# DriverOK-DemuxOK-VIA71.net
KiCad netlist of a schematic drawn in EAGLE
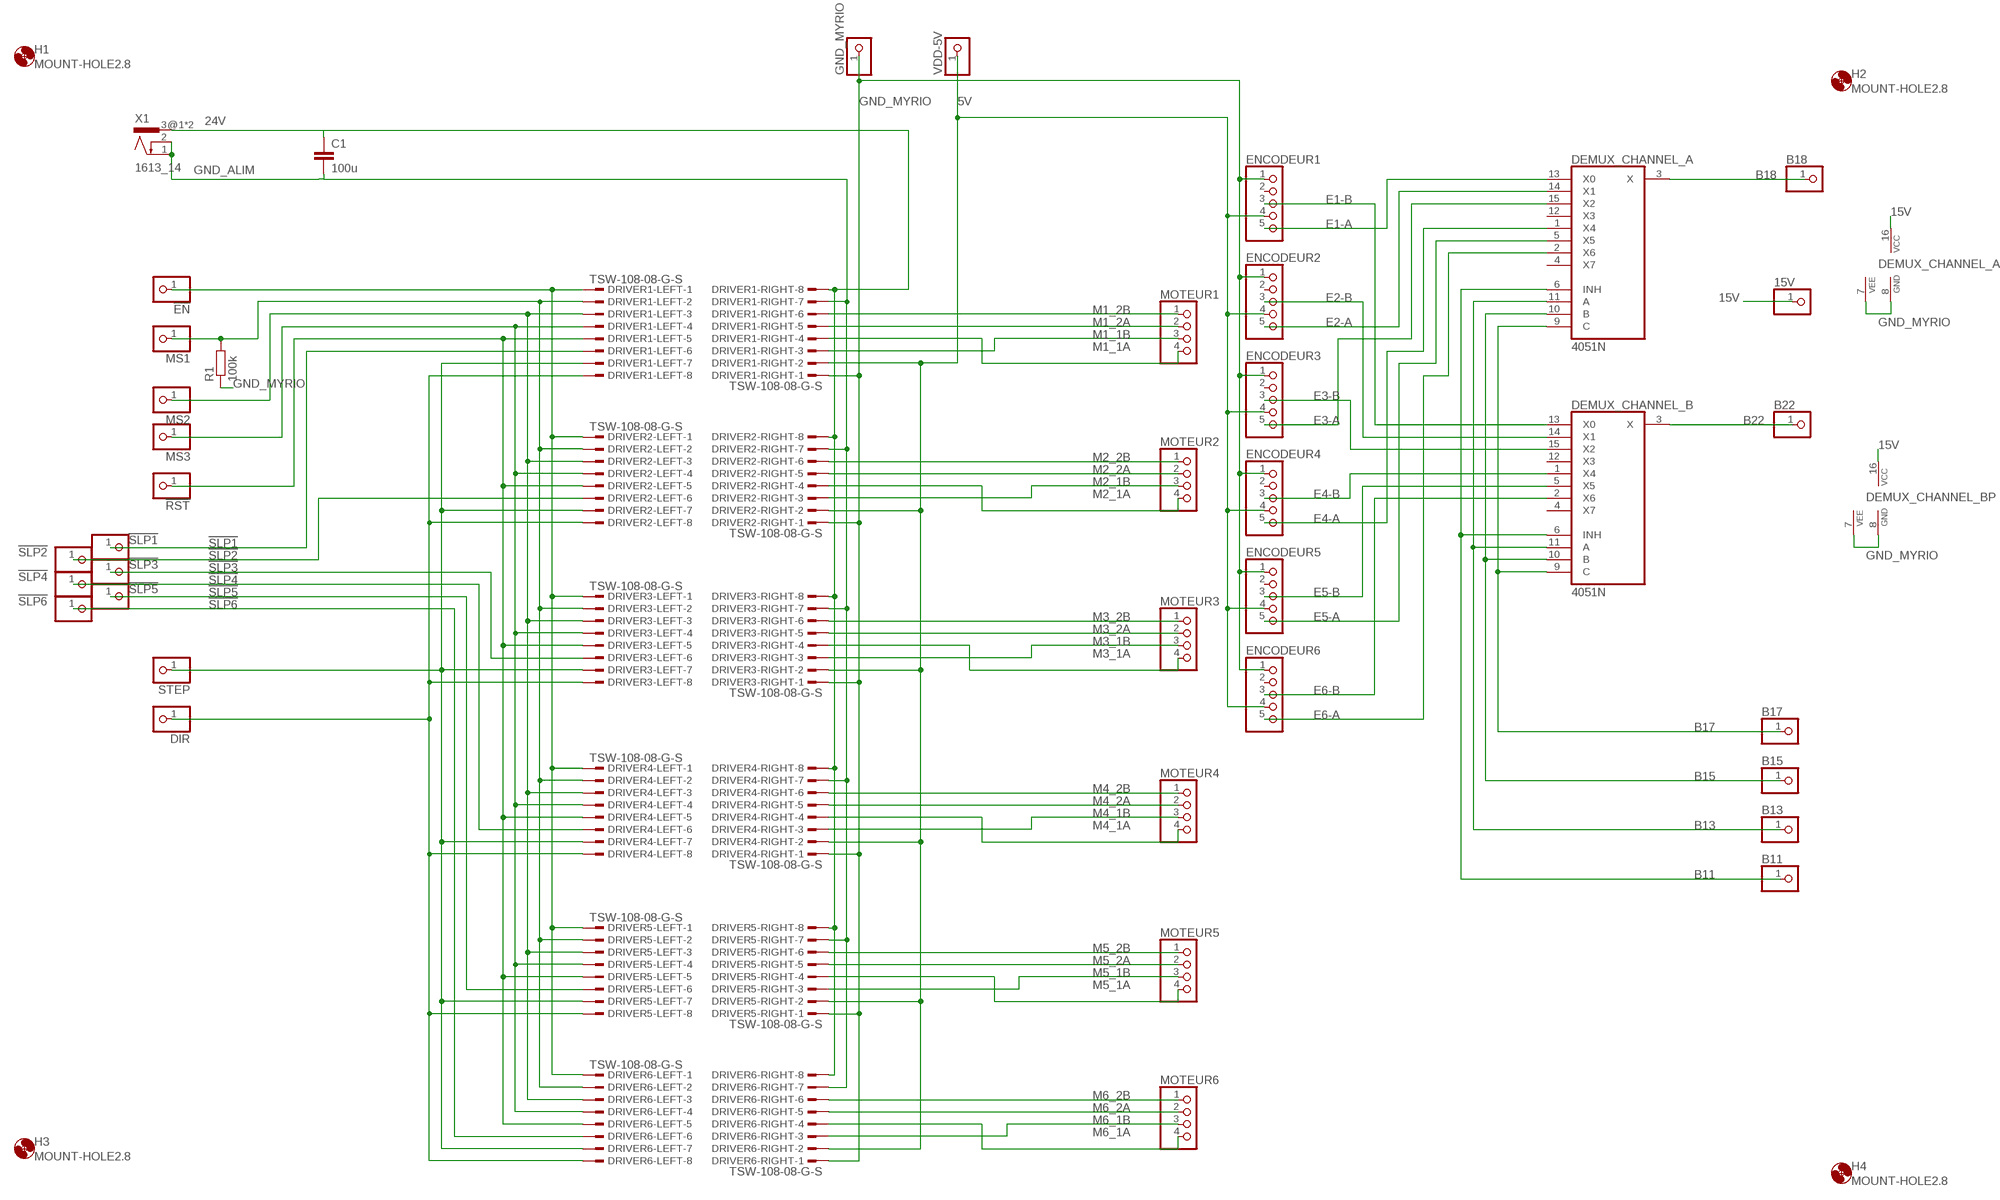
[diagram p0: schematic, sheet 1]

(export (version "E")
  (design (tool "Eeschema 10.0.6"))
  (components
    (comp (ref "!EN")
      (value "PINHD-1X1")
      (footprint "eagle-import:1X01")
      (libsource (lib "eagle-import") (part "PINHD-1X1"))
    )
    (comp (ref "!RST")
      (value "PINHD-1X1")
      (footprint "eagle-import:1X01")
      (libsource (lib "eagle-import") (part "PINHD-1X1"))
    )
    (comp (ref "!SLP1")
      (value "PINHD-1X1")
      (footprint "eagle-import:1X01")
      (libsource (lib "eagle-import") (part "PINHD-1X1"))
    )
    (comp (ref "!SLP2")
      (value "PINHD-1X1")
      (footprint "eagle-import:1X01")
      (libsource (lib "eagle-import") (part "PINHD-1X1"))
    )
    (comp (ref "!SLP3")
      (value "PINHD-1X1")
      (footprint "eagle-import:1X01")
      (libsource (lib "eagle-import") (part "PINHD-1X1"))
    )
    (comp (ref "!SLP4")
      (value "PINHD-1X1")
      (footprint "eagle-import:1X01")
      (libsource (lib "eagle-import") (part "PINHD-1X1"))
    )
    (comp (ref "!SLP5")
      (value "PINHD-1X1")
      (footprint "eagle-import:1X01")
      (libsource (lib "eagle-import") (part "PINHD-1X1"))
    )
    (comp (ref "!SLP6")
      (value "PINHD-1X1")
      (footprint "eagle-import:1X01")
      (libsource (lib "eagle-import") (part "PINHD-1X1"))
    )
    (comp (ref "15V")
      (value "PINHD-1X1")
      (footprint "eagle-import:1X01")
      (libsource (lib "eagle-import") (part "PINHD-1X1"))
    )
    (comp (ref "B11")
      (value "PINHD-1X1")
      (footprint "eagle-import:1X01")
      (libsource (lib "eagle-import") (part "PINHD-1X1"))
    )
    (comp (ref "B13")
      (value "PINHD-1X1")
      (footprint "eagle-import:1X01")
      (libsource (lib "eagle-import") (part "PINHD-1X1"))
    )
    (comp (ref "B15")
      (value "PINHD-1X1")
      (footprint "eagle-import:1X01")
      (libsource (lib "eagle-import") (part "PINHD-1X1"))
    )
    (comp (ref "B17")
      (value "PINHD-1X1")
      (footprint "eagle-import:1X01")
      (libsource (lib "eagle-import") (part "PINHD-1X1"))
    )
    (comp (ref "B18")
      (value "PINHD-1X1")
      (footprint "eagle-import:1X01")
      (libsource (lib "eagle-import") (part "PINHD-1X1"))
    )
    (comp (ref "B22")
      (value "PINHD-1X1")
      (footprint "eagle-import:1X01")
      (libsource (lib "eagle-import") (part "PINHD-1X1"))
    )
    (comp (ref "C1")
      (value "100u")
      (footprint "eagle-import:C025-025X050")
      (libsource (lib "eagle-import") (part "C-EU025-025X050"))
    )
    (comp (ref "DEMUX_CHANNEL_A")
      (value "4051N")
      (footprint "eagle-import:DIL16")
      (libsource (lib "eagle-import") (part "4051N"))
    )
    (comp (ref "DEMUX_CHANNEL_B")
      (value "4051N")
      (footprint "eagle-import:DIL16")
      (libsource (lib "eagle-import") (part "4051N"))
    )
    (comp (ref "DIR")
      (value "PINHD-1X1")
      (footprint "eagle-import:1X01")
      (libsource (lib "eagle-import") (part "PINHD-1X1"))
    )
    (comp (ref "DRIVER1-LEFT")
      (value "TSW-108-08-G-S")
      (footprint "eagle-import:TSW-108-XX-G-S")
      (fields (field (name "MF") "Samtec Inc.") (field (name "MPN") "TSW-108-07-G-S"))
      (libsource (lib "eagle-import") (part "TSW-108--G-S08"))
    )
    (comp (ref "DRIVER1-RIGHT")
      (value "TSW-108-08-G-S")
      (footprint "eagle-import:TSW-108-XX-G-S")
      (fields (field (name "MF") "Samtec Inc.") (field (name "MPN") "TSW-108-07-G-S"))
      (libsource (lib "eagle-import") (part "TSW-108--G-S08"))
    )
    (comp (ref "DRIVER2-LEFT")
      (value "TSW-108-08-G-S")
      (footprint "eagle-import:TSW-108-XX-G-S")
      (fields (field (name "MF") "Samtec Inc.") (field (name "MPN") "TSW-108-07-G-S"))
      (libsource (lib "eagle-import") (part "TSW-108--G-S08"))
    )
    (comp (ref "DRIVER2-RIGHT")
      (value "TSW-108-08-G-S")
      (footprint "eagle-import:TSW-108-XX-G-S")
      (fields (field (name "MF") "Samtec Inc.") (field (name "MPN") "TSW-108-07-G-S"))
      (libsource (lib "eagle-import") (part "TSW-108--G-S08"))
    )
    (comp (ref "DRIVER3-LEFT")
      (value "TSW-108-08-G-S")
      (footprint "eagle-import:TSW-108-XX-G-S")
      (fields (field (name "MF") "Samtec Inc.") (field (name "MPN") "TSW-108-07-G-S"))
      (libsource (lib "eagle-import") (part "TSW-108--G-S08"))
    )
    (comp (ref "DRIVER3-RIGHT")
      (value "TSW-108-08-G-S")
      (footprint "eagle-import:TSW-108-XX-G-S")
      (fields (field (name "MF") "Samtec Inc.") (field (name "MPN") "TSW-108-07-G-S"))
      (libsource (lib "eagle-import") (part "TSW-108--G-S08"))
    )
    (comp (ref "DRIVER4-LEFT")
      (value "TSW-108-08-G-S")
      (footprint "eagle-import:TSW-108-XX-G-S")
      (fields (field (name "MF") "Samtec Inc.") (field (name "MPN") "TSW-108-07-G-S"))
      (libsource (lib "eagle-import") (part "TSW-108--G-S08"))
    )
    (comp (ref "DRIVER4-RIGHT")
      (value "TSW-108-08-G-S")
      (footprint "eagle-import:TSW-108-XX-G-S")
      (fields (field (name "MF") "Samtec Inc.") (field (name "MPN") "TSW-108-07-G-S"))
      (libsource (lib "eagle-import") (part "TSW-108--G-S08"))
    )
    (comp (ref "DRIVER5-LEFT")
      (value "TSW-108-08-G-S")
      (footprint "eagle-import:TSW-108-XX-G-S")
      (fields (field (name "MF") "Samtec Inc.") (field (name "MPN") "TSW-108-07-G-S"))
      (libsource (lib "eagle-import") (part "TSW-108--G-S08"))
    )
    (comp (ref "DRIVER5-RIGHT")
      (value "TSW-108-08-G-S")
      (footprint "eagle-import:TSW-108-XX-G-S")
      (fields (field (name "MF") "Samtec Inc.") (field (name "MPN") "TSW-108-07-G-S"))
      (libsource (lib "eagle-import") (part "TSW-108--G-S08"))
    )
    (comp (ref "DRIVER6-LEFT")
      (value "TSW-108-08-G-S")
      (footprint "eagle-import:TSW-108-XX-G-S")
      (fields (field (name "MF") "Samtec Inc.") (field (name "MPN") "TSW-108-07-G-S"))
      (libsource (lib "eagle-import") (part "TSW-108--G-S08"))
    )
    (comp (ref "DRIVER6-RIGHT")
      (value "TSW-108-08-G-S")
      (footprint "eagle-import:TSW-108-XX-G-S")
      (fields (field (name "MF") "Samtec Inc.") (field (name "MPN") "TSW-108-07-G-S"))
      (libsource (lib "eagle-import") (part "TSW-108--G-S08"))
    )
    (comp (ref "ENCODEUR1")
      (value "PINHD-1X5")
      (footprint "eagle-import:1X05")
      (libsource (lib "eagle-import") (part "PINHD-1X5"))
    )
    (comp (ref "ENCODEUR2")
      (value "PINHD-1X5")
      (footprint "eagle-import:1X05")
      (libsource (lib "eagle-import") (part "PINHD-1X5"))
    )
    (comp (ref "ENCODEUR3")
      (value "PINHD-1X5")
      (footprint "eagle-import:1X05")
      (libsource (lib "eagle-import") (part "PINHD-1X5"))
    )
    (comp (ref "ENCODEUR4")
      (value "PINHD-1X5")
      (footprint "eagle-import:1X05")
      (libsource (lib "eagle-import") (part "PINHD-1X5"))
    )
    (comp (ref "ENCODEUR5")
      (value "PINHD-1X5")
      (footprint "eagle-import:1X05")
      (libsource (lib "eagle-import") (part "PINHD-1X5"))
    )
    (comp (ref "ENCODEUR6")
      (value "PINHD-1X5")
      (footprint "eagle-import:1X05")
      (libsource (lib "eagle-import") (part "PINHD-1X5"))
    )
    (comp (ref "GND_MYRIO")
      (value "PINHD-1X1")
      (footprint "eagle-import:1X01")
      (libsource (lib "eagle-import") (part "PINHD-1X1"))
    )
    (comp (ref "H1")
      (value "MOUNT-HOLE2.8")
      (footprint "eagle-import:2,8")
      (libsource (lib "eagle-import") (part "MOUNT-HOLE2.8"))
    )
    (comp (ref "H2")
      (value "MOUNT-HOLE2.8")
      (footprint "eagle-import:2,8")
      (libsource (lib "eagle-import") (part "MOUNT-HOLE2.8"))
    )
    (comp (ref "H3")
      (value "MOUNT-HOLE2.8")
      (footprint "eagle-import:2,8")
      (libsource (lib "eagle-import") (part "MOUNT-HOLE2.8"))
    )
    (comp (ref "H4")
      (value "MOUNT-HOLE2.8")
      (footprint "eagle-import:2,8")
      (libsource (lib "eagle-import") (part "MOUNT-HOLE2.8"))
    )
    (comp (ref "MOTEUR1")
      (value "PINHD-1X4")
      (footprint "eagle-import:1X04")
      (libsource (lib "eagle-import") (part "PINHD-1X4"))
    )
    (comp (ref "MOTEUR2")
      (value "PINHD-1X4")
      (footprint "eagle-import:1X04")
      (libsource (lib "eagle-import") (part "PINHD-1X4"))
    )
    (comp (ref "MOTEUR3")
      (value "PINHD-1X4")
      (footprint "eagle-import:1X04")
      (libsource (lib "eagle-import") (part "PINHD-1X4"))
    )
    (comp (ref "MOTEUR4")
      (value "PINHD-1X4")
      (footprint "eagle-import:1X04")
      (libsource (lib "eagle-import") (part "PINHD-1X4"))
    )
    (comp (ref "MOTEUR5")
      (value "PINHD-1X4")
      (footprint "eagle-import:1X04")
      (libsource (lib "eagle-import") (part "PINHD-1X4"))
    )
    (comp (ref "MOTEUR6")
      (value "PINHD-1X4")
      (footprint "eagle-import:1X04")
      (libsource (lib "eagle-import") (part "PINHD-1X4"))
    )
    (comp (ref "MS1")
      (value "PINHD-1X1")
      (footprint "eagle-import:1X01")
      (libsource (lib "eagle-import") (part "PINHD-1X1"))
    )
    (comp (ref "MS2")
      (value "PINHD-1X1")
      (footprint "eagle-import:1X01")
      (libsource (lib "eagle-import") (part "PINHD-1X1"))
    )
    (comp (ref "MS3")
      (value "PINHD-1X1")
      (footprint "eagle-import:1X01")
      (libsource (lib "eagle-import") (part "PINHD-1X1"))
    )
    (comp (ref "R1")
      (value "100k")
      (footprint "eagle-import:0207_10")
      (libsource (lib "eagle-import") (part "R-EU_0207/10"))
    )
    (comp (ref "STEP")
      (value "PINHD-1X1")
      (footprint "eagle-import:1X01")
      (libsource (lib "eagle-import") (part "PINHD-1X1"))
    )
    (comp (ref "VDD-5V")
      (value "PINHD-1X1")
      (footprint "eagle-import:1X01")
      (libsource (lib "eagle-import") (part "PINHD-1X1"))
    )
    (comp (ref "X1")
      (value "1613_14")
      (footprint "eagle-import:1613_14")
      (fields (field (name "MF") "LUMBERG") (field (name "MPN") "1613 14"))
      (libsource (lib "eagle-import") (part "1613_14"))
    )
  )
  (nets
    (net (code "1") (name "/5V") (class "Default")
      (node (ref "DRIVER1-RIGHT") (pin "2") (pinfunction "1_2") (pintype "passive"))
      (node (ref "DRIVER2-RIGHT") (pin "2") (pinfunction "1_2") (pintype "passive"))
      (node (ref "DRIVER3-RIGHT") (pin "2") (pinfunction "1_2") (pintype "passive"))
      (node (ref "DRIVER4-RIGHT") (pin "2") (pinfunction "1_2") (pintype "passive"))
      (node (ref "DRIVER5-RIGHT") (pin "2") (pinfunction "1_2") (pintype "passive"))
      (node (ref "DRIVER6-RIGHT") (pin "2") (pinfunction "1_2") (pintype "passive"))
      (node (ref "ENCODEUR1") (pin "4") (pinfunction "4_4") (pintype "passive"))
      (node (ref "ENCODEUR2") (pin "4") (pinfunction "4_4") (pintype "passive"))
      (node (ref "ENCODEUR3") (pin "4") (pinfunction "4_4") (pintype "passive"))
      (node (ref "ENCODEUR4") (pin "4") (pinfunction "4_4") (pintype "passive"))
      (node (ref "ENCODEUR5") (pin "4") (pinfunction "4_4") (pintype "passive"))
      (node (ref "ENCODEUR6") (pin "4") (pinfunction "4_4") (pintype "passive"))
      (node (ref "VDD-5V") (pin "1") (pinfunction "1_1") (pintype "passive"))
    )
    (net (code "2") (name "/15V") (class "Default")
      (node (ref "15V") (pin "1") (pinfunction "1_1") (pintype "passive"))
      (node (ref "DEMUX_CHANNEL_A") (pin "16") (pinfunction "VCC_16") (pintype "power_in"))
      (node (ref "DEMUX_CHANNEL_B") (pin "16") (pinfunction "VCC_16") (pintype "power_in"))
    )
    (net (code "3") (name "/24V") (class "Default")
      (node (ref "C1") (pin "1") (pinfunction "1_1") (pintype "passive"))
      (node (ref "DRIVER1-RIGHT") (pin "8") (pinfunction "1_8") (pintype "passive"))
      (node (ref "DRIVER2-RIGHT") (pin "8") (pinfunction "1_8") (pintype "passive"))
      (node (ref "DRIVER3-RIGHT") (pin "8") (pinfunction "1_8") (pintype "passive"))
      (node (ref "DRIVER4-RIGHT") (pin "8") (pinfunction "1_8") (pintype "passive"))
      (node (ref "DRIVER5-RIGHT") (pin "8") (pinfunction "1_8") (pintype "passive"))
      (node (ref "DRIVER6-RIGHT") (pin "8") (pinfunction "1_8") (pintype "passive"))
      (node (ref "X1") (pin "3@1") (pinfunction "3_3@1") (pintype "passive"))
      (node (ref "X1") (pin "3@2") (pinfunction "3_3@2") (pintype "passive"))
    )
    (net (code "4") (name "/B11") (class "Default")
      (node (ref "B11") (pin "1") (pinfunction "1_1") (pintype "passive"))
      (node (ref "DEMUX_CHANNEL_A") (pin "6") (pinfunction "INH_6") (pintype "input"))
      (node (ref "DEMUX_CHANNEL_B") (pin "6") (pinfunction "INH_6") (pintype "input"))
    )
    (net (code "5") (name "/B13") (class "Default")
      (node (ref "B13") (pin "1") (pinfunction "1_1") (pintype "passive"))
      (node (ref "DEMUX_CHANNEL_A") (pin "11") (pinfunction "A_11") (pintype "input"))
      (node (ref "DEMUX_CHANNEL_B") (pin "11") (pinfunction "A_11") (pintype "input"))
    )
    (net (code "6") (name "/B15") (class "Default")
      (node (ref "B15") (pin "1") (pinfunction "1_1") (pintype "passive"))
      (node (ref "DEMUX_CHANNEL_A") (pin "10") (pinfunction "B_10") (pintype "input"))
      (node (ref "DEMUX_CHANNEL_B") (pin "10") (pinfunction "B_10") (pintype "input"))
    )
    (net (code "7") (name "/B17") (class "Default")
      (node (ref "B17") (pin "1") (pinfunction "1_1") (pintype "passive"))
      (node (ref "DEMUX_CHANNEL_A") (pin "9") (pinfunction "C_9") (pintype "input"))
      (node (ref "DEMUX_CHANNEL_B") (pin "9") (pinfunction "C_9") (pintype "input"))
    )
    (net (code "8") (name "/B18") (class "Default")
      (node (ref "B18") (pin "1") (pinfunction "1_1") (pintype "passive"))
      (node (ref "DEMUX_CHANNEL_A") (pin "3") (pinfunction "X_3") (pintype "bidirectional"))
    )
    (net (code "9") (name "/B22") (class "Default")
      (node (ref "B22") (pin "1") (pinfunction "1_1") (pintype "passive"))
      (node (ref "DEMUX_CHANNEL_B") (pin "3") (pinfunction "X_3") (pintype "bidirectional"))
    )
    (net (code "10") (name "/E1-A") (class "Default")
      (node (ref "DEMUX_CHANNEL_A") (pin "13") (pinfunction "X0_13") (pintype "bidirectional"))
      (node (ref "ENCODEUR1") (pin "5") (pinfunction "5_5") (pintype "passive"))
    )
    (net (code "11") (name "/E1-B") (class "Default")
      (node (ref "DEMUX_CHANNEL_B") (pin "13") (pinfunction "X0_13") (pintype "bidirectional"))
      (node (ref "ENCODEUR1") (pin "3") (pinfunction "3_3") (pintype "passive"))
    )
    (net (code "12") (name "/E2-A") (class "Default")
      (node (ref "DEMUX_CHANNEL_A") (pin "14") (pinfunction "X1_14") (pintype "bidirectional"))
      (node (ref "ENCODEUR2") (pin "5") (pinfunction "5_5") (pintype "passive"))
    )
    (net (code "13") (name "/E2-B") (class "Default")
      (node (ref "DEMUX_CHANNEL_B") (pin "14") (pinfunction "X1_14") (pintype "bidirectional"))
      (node (ref "ENCODEUR2") (pin "3") (pinfunction "3_3") (pintype "passive"))
    )
    (net (code "14") (name "/E3-A") (class "Default")
      (node (ref "DEMUX_CHANNEL_A") (pin "15") (pinfunction "X2_15") (pintype "bidirectional"))
      (node (ref "ENCODEUR3") (pin "5") (pinfunction "5_5") (pintype "passive"))
    )
    (net (code "15") (name "/E3-B") (class "Default")
      (node (ref "DEMUX_CHANNEL_B") (pin "15") (pinfunction "X2_15") (pintype "bidirectional"))
      (node (ref "ENCODEUR3") (pin "3") (pinfunction "3_3") (pintype "passive"))
    )
    (net (code "16") (name "/E4-A") (class "Default")
      (node (ref "DEMUX_CHANNEL_A") (pin "1") (pinfunction "X4_1") (pintype "bidirectional"))
      (node (ref "ENCODEUR4") (pin "5") (pinfunction "5_5") (pintype "passive"))
    )
    (net (code "17") (name "/E4-B") (class "Default")
      (node (ref "DEMUX_CHANNEL_B") (pin "1") (pinfunction "X4_1") (pintype "bidirectional"))
      (node (ref "ENCODEUR4") (pin "3") (pinfunction "3_3") (pintype "passive"))
    )
    (net (code "18") (name "/E5-A") (class "Default")
      (node (ref "DEMUX_CHANNEL_A") (pin "5") (pinfunction "X5_5") (pintype "bidirectional"))
      (node (ref "ENCODEUR5") (pin "5") (pinfunction "5_5") (pintype "passive"))
    )
    (net (code "19") (name "/E5-B") (class "Default")
      (node (ref "DEMUX_CHANNEL_B") (pin "5") (pinfunction "X5_5") (pintype "bidirectional"))
      (node (ref "ENCODEUR5") (pin "3") (pinfunction "3_3") (pintype "passive"))
    )
    (net (code "20") (name "/E6-A") (class "Default")
      (node (ref "DEMUX_CHANNEL_A") (pin "2") (pinfunction "X6_2") (pintype "bidirectional"))
      (node (ref "ENCODEUR6") (pin "5") (pinfunction "5_5") (pintype "passive"))
    )
    (net (code "21") (name "/E6-B") (class "Default")
      (node (ref "DEMUX_CHANNEL_B") (pin "2") (pinfunction "X6_2") (pintype "bidirectional"))
      (node (ref "ENCODEUR6") (pin "3") (pinfunction "3_3") (pintype "passive"))
    )
    (net (code "22") (name "/GND_ALIM") (class "Default")
      (node (ref "C1") (pin "2") (pinfunction "2_2") (pintype "passive"))
      (node (ref "DRIVER1-RIGHT") (pin "7") (pinfunction "1_7") (pintype "passive"))
      (node (ref "DRIVER2-RIGHT") (pin "7") (pinfunction "1_7") (pintype "passive"))
      (node (ref "DRIVER3-RIGHT") (pin "7") (pinfunction "1_7") (pintype "passive"))
      (node (ref "DRIVER4-RIGHT") (pin "7") (pinfunction "1_7") (pintype "passive"))
      (node (ref "DRIVER5-RIGHT") (pin "7") (pinfunction "1_7") (pintype "passive"))
      (node (ref "DRIVER6-RIGHT") (pin "7") (pinfunction "1_7") (pintype "passive"))
      (node (ref "X1") (pin "1") (pinfunction "1_1") (pintype "passive"))
      (node (ref "X1") (pin "2") (pinfunction "2_2") (pintype "passive"))
    )
    (net (code "23") (name "/GND_MYRIO") (class "Default")
      (node (ref "DEMUX_CHANNEL_A") (pin "7") (pinfunction "VEE_7") (pintype "power_in"))
      (node (ref "DEMUX_CHANNEL_A") (pin "8") (pinfunction "GND_8") (pintype "power_in"))
      (node (ref "DEMUX_CHANNEL_B") (pin "7") (pinfunction "VEE_7") (pintype "power_in"))
      (node (ref "DEMUX_CHANNEL_B") (pin "8") (pinfunction "GND_8") (pintype "power_in"))
      (node (ref "DRIVER1-RIGHT") (pin "1") (pinfunction "1_1") (pintype "passive"))
      (node (ref "DRIVER2-RIGHT") (pin "1") (pinfunction "1_1") (pintype "passive"))
      (node (ref "DRIVER3-RIGHT") (pin "1") (pinfunction "1_1") (pintype "passive"))
      (node (ref "DRIVER4-RIGHT") (pin "1") (pinfunction "1_1") (pintype "passive"))
      (node (ref "DRIVER5-RIGHT") (pin "1") (pinfunction "1_1") (pintype "passive"))
      (node (ref "DRIVER6-RIGHT") (pin "1") (pinfunction "1_1") (pintype "passive"))
      (node (ref "ENCODEUR1") (pin "1") (pinfunction "1_1") (pintype "passive"))
      (node (ref "ENCODEUR2") (pin "1") (pinfunction "1_1") (pintype "passive"))
      (node (ref "ENCODEUR3") (pin "1") (pinfunction "1_1") (pintype "passive"))
      (node (ref "ENCODEUR4") (pin "1") (pinfunction "1_1") (pintype "passive"))
      (node (ref "ENCODEUR5") (pin "1") (pinfunction "1_1") (pintype "passive"))
      (node (ref "ENCODEUR6") (pin "1") (pinfunction "1_1") (pintype "passive"))
      (node (ref "GND_MYRIO") (pin "1") (pinfunction "1_1") (pintype "passive"))
      (node (ref "R1") (pin "1") (pinfunction "1_1") (pintype "passive"))
    )
    (net (code "24") (name "/M1_1A") (class "Default")
      (node (ref "DRIVER1-RIGHT") (pin "4") (pinfunction "1_4") (pintype "passive"))
      (node (ref "MOTEUR1") (pin "4") (pinfunction "4_4") (pintype "passive"))
    )
    (net (code "25") (name "/M1_1B") (class "Default")
      (node (ref "DRIVER1-RIGHT") (pin "3") (pinfunction "1_3") (pintype "passive"))
      (node (ref "MOTEUR1") (pin "3") (pinfunction "3_3") (pintype "passive"))
    )
    (net (code "26") (name "/M1_2A") (class "Default")
      (node (ref "DRIVER1-RIGHT") (pin "5") (pinfunction "1_5") (pintype "passive"))
      (node (ref "MOTEUR1") (pin "2") (pinfunction "2_2") (pintype "passive"))
    )
    (net (code "27") (name "/M1_2B") (class "Default")
      (node (ref "DRIVER1-RIGHT") (pin "6") (pinfunction "1_6") (pintype "passive"))
      (node (ref "MOTEUR1") (pin "1") (pinfunction "1_1") (pintype "passive"))
    )
    (net (code "28") (name "/M2_1A") (class "Default")
      (node (ref "DRIVER2-RIGHT") (pin "4") (pinfunction "1_4") (pintype "passive"))
      (node (ref "MOTEUR2") (pin "4") (pinfunction "4_4") (pintype "passive"))
    )
    (net (code "29") (name "/M2_1B") (class "Default")
      (node (ref "DRIVER2-RIGHT") (pin "3") (pinfunction "1_3") (pintype "passive"))
      (node (ref "MOTEUR2") (pin "3") (pinfunction "3_3") (pintype "passive"))
    )
    (net (code "30") (name "/M2_2A") (class "Default")
      (node (ref "DRIVER2-RIGHT") (pin "5") (pinfunction "1_5") (pintype "passive"))
      (node (ref "MOTEUR2") (pin "2") (pinfunction "2_2") (pintype "passive"))
    )
    (net (code "31") (name "/M2_2B") (class "Default")
      (node (ref "DRIVER2-RIGHT") (pin "6") (pinfunction "1_6") (pintype "passive"))
      (node (ref "MOTEUR2") (pin "1") (pinfunction "1_1") (pintype "passive"))
    )
    (net (code "32") (name "/M3_1A") (class "Default")
      (node (ref "DRIVER3-RIGHT") (pin "4") (pinfunction "1_4") (pintype "passive"))
      (node (ref "MOTEUR3") (pin "4") (pinfunction "4_4") (pintype "passive"))
    )
    (net (code "33") (name "/M3_1B") (class "Default")
      (node (ref "DRIVER3-RIGHT") (pin "3") (pinfunction "1_3") (pintype "passive"))
      (node (ref "MOTEUR3") (pin "3") (pinfunction "3_3") (pintype "passive"))
    )
    (net (code "34") (name "/M3_2A") (class "Default")
      (node (ref "DRIVER3-RIGHT") (pin "5") (pinfunction "1_5") (pintype "passive"))
      (node (ref "MOTEUR3") (pin "2") (pinfunction "2_2") (pintype "passive"))
    )
    (net (code "35") (name "/M3_2B") (class "Default")
      (node (ref "DRIVER3-RIGHT") (pin "6") (pinfunction "1_6") (pintype "passive"))
      (node (ref "MOTEUR3") (pin "1") (pinfunction "1_1") (pintype "passive"))
    )
    (net (code "36") (name "/M4_1A") (class "Default")
      (node (ref "DRIVER4-RIGHT") (pin "4") (pinfunction "1_4") (pintype "passive"))
      (node (ref "MOTEUR4") (pin "4") (pinfunction "4_4") (pintype "passive"))
    )
    (net (code "37") (name "/M4_1B") (class "Default")
      (node (ref "DRIVER4-RIGHT") (pin "3") (pinfunction "1_3") (pintype "passive"))
      (node (ref "MOTEUR4") (pin "3") (pinfunction "3_3") (pintype "passive"))
    )
    (net (code "38") (name "/M4_2A") (class "Default")
      (node (ref "DRIVER4-RIGHT") (pin "5") (pinfunction "1_5") (pintype "passive"))
      (node (ref "MOTEUR4") (pin "2") (pinfunction "2_2") (pintype "passive"))
    )
    (net (code "39") (name "/M4_2B") (class "Default")
      (node (ref "DRIVER4-RIGHT") (pin "6") (pinfunction "1_6") (pintype "passive"))
      (node (ref "MOTEUR4") (pin "1") (pinfunction "1_1") (pintype "passive"))
    )
    (net (code "40") (name "/M5_1A") (class "Default")
      (node (ref "DRIVER5-RIGHT") (pin "4") (pinfunction "1_4") (pintype "passive"))
      (node (ref "MOTEUR5") (pin "4") (pinfunction "4_4") (pintype "passive"))
    )
    (net (code "41") (name "/M5_1B") (class "Default")
      (node (ref "DRIVER5-RIGHT") (pin "3") (pinfunction "1_3") (pintype "passive"))
      (node (ref "MOTEUR5") (pin "3") (pinfunction "3_3") (pintype "passive"))
    )
    (net (code "42") (name "/M5_2A") (class "Default")
      (node (ref "DRIVER5-RIGHT") (pin "5") (pinfunction "1_5") (pintype "passive"))
      (node (ref "MOTEUR5") (pin "2") (pinfunction "2_2") (pintype "passive"))
    )
    (net (code "43") (name "/M5_2B") (class "Default")
      (node (ref "DRIVER5-RIGHT") (pin "6") (pinfunction "1_6") (pintype "passive"))
      (node (ref "MOTEUR5") (pin "1") (pinfunction "1_1") (pintype "passive"))
    )
    (net (code "44") (name "/M6_1A") (class "Default")
      (node (ref "DRIVER6-RIGHT") (pin "4") (pinfunction "1_4") (pintype "passive"))
      (node (ref "MOTEUR6") (pin "4") (pinfunction "4_4") (pintype "passive"))
    )
    (net (code "45") (name "/M6_1B") (class "Default")
      (node (ref "DRIVER6-RIGHT") (pin "3") (pinfunction "1_3") (pintype "passive"))
      (node (ref "MOTEUR6") (pin "3") (pinfunction "3_3") (pintype "passive"))
    )
    (net (code "46") (name "/M6_2A") (class "Default")
      (node (ref "DRIVER6-RIGHT") (pin "5") (pinfunction "1_5") (pintype "passive"))
      (node (ref "MOTEUR6") (pin "2") (pinfunction "2_2") (pintype "passive"))
    )
    (net (code "47") (name "/M6_2B") (class "Default")
      (node (ref "DRIVER6-RIGHT") (pin "6") (pinfunction "1_6") (pintype "passive"))
      (node (ref "MOTEUR6") (pin "1") (pinfunction "1_1") (pintype "passive"))
    )
    (net (code "48") (name "/~{SLP1}") (class "Default")
      (node (ref "!SLP1") (pin "1") (pinfunction "1_1") (pintype "passive"))
      (node (ref "DRIVER1-LEFT") (pin "6") (pinfunction "1_6") (pintype "passive"))
    )
    (net (code "49") (name "/~{SLP2}") (class "Default")
      (node (ref "!SLP2") (pin "1") (pinfunction "1_1") (pintype "passive"))
      (node (ref "DRIVER2-LEFT") (pin "6") (pinfunction "1_6") (pintype "passive"))
    )
    (net (code "50") (name "/~{SLP3}") (class "Default")
      (node (ref "!SLP3") (pin "1") (pinfunction "1_1") (pintype "passive"))
      (node (ref "DRIVER3-LEFT") (pin "6") (pinfunction "1_6") (pintype "passive"))
    )
    (net (code "51") (name "/~{SLP4}") (class "Default")
      (node (ref "!SLP4") (pin "1") (pinfunction "1_1") (pintype "passive"))
      (node (ref "DRIVER4-LEFT") (pin "6") (pinfunction "1_6") (pintype "passive"))
    )
    (net (code "52") (name "/~{SLP5}") (class "Default")
      (node (ref "!SLP5") (pin "1") (pinfunction "1_1") (pintype "passive"))
      (node (ref "DRIVER5-LEFT") (pin "6") (pinfunction "1_6") (pintype "passive"))
    )
    (net (code "53") (name "/~{SLP6}") (class "Default")
      (node (ref "!SLP6") (pin "1") (pinfunction "1_1") (pintype "passive"))
      (node (ref "DRIVER6-LEFT") (pin "6") (pinfunction "1_6") (pintype "passive"))
    )
    (net (code "54") (name "Net-(!EN-Pad1)") (class "Default")
      (node (ref "!EN") (pin "1") (pinfunction "1_1") (pintype "passive"))
      (node (ref "DRIVER1-LEFT") (pin "1") (pinfunction "1_1") (pintype "passive"))
      (node (ref "DRIVER2-LEFT") (pin "1") (pinfunction "1_1") (pintype "passive"))
      (node (ref "DRIVER3-LEFT") (pin "1") (pinfunction "1_1") (pintype "passive"))
      (node (ref "DRIVER4-LEFT") (pin "1") (pinfunction "1_1") (pintype "passive"))
      (node (ref "DRIVER5-LEFT") (pin "1") (pinfunction "1_1") (pintype "passive"))
      (node (ref "DRIVER6-LEFT") (pin "1") (pinfunction "1_1") (pintype "passive"))
    )
    (net (code "55") (name "Net-(DRIVER1-LEFTB-1)") (class "Default")
      (node (ref "DRIVER1-LEFT") (pin "2") (pinfunction "1_2") (pintype "passive"))
      (node (ref "DRIVER2-LEFT") (pin "2") (pinfunction "1_2") (pintype "passive"))
      (node (ref "DRIVER3-LEFT") (pin "2") (pinfunction "1_2") (pintype "passive"))
      (node (ref "DRIVER4-LEFT") (pin "2") (pinfunction "1_2") (pintype "passive"))
      (node (ref "DRIVER5-LEFT") (pin "2") (pinfunction "1_2") (pintype "passive"))
      (node (ref "DRIVER6-LEFT") (pin "2") (pinfunction "1_2") (pintype "passive"))
      (node (ref "MS1") (pin "1") (pinfunction "1_1") (pintype "passive"))
      (node (ref "R1") (pin "2") (pinfunction "2_2") (pintype "passive"))
    )
    (net (code "56") (name "Net-(DRIVER1-LEFTC-1)") (class "Default")
      (node (ref "DRIVER1-LEFT") (pin "3") (pinfunction "1_3") (pintype "passive"))
      (node (ref "DRIVER2-LEFT") (pin "3") (pinfunction "1_3") (pintype "passive"))
      (node (ref "DRIVER3-LEFT") (pin "3") (pinfunction "1_3") (pintype "passive"))
      (node (ref "DRIVER4-LEFT") (pin "3") (pinfunction "1_3") (pintype "passive"))
      (node (ref "DRIVER5-LEFT") (pin "3") (pinfunction "1_3") (pintype "passive"))
      (node (ref "DRIVER6-LEFT") (pin "3") (pinfunction "1_3") (pintype "passive"))
      (node (ref "MS2") (pin "1") (pinfunction "1_1") (pintype "passive"))
    )
    (net (code "57") (name "Net-(DRIVER1-LEFTD-1)") (class "Default")
      (node (ref "DRIVER1-LEFT") (pin "4") (pinfunction "1_4") (pintype "passive"))
      (node (ref "DRIVER2-LEFT") (pin "4") (pinfunction "1_4") (pintype "passive"))
      (node (ref "DRIVER3-LEFT") (pin "4") (pinfunction "1_4") (pintype "passive"))
      (node (ref "DRIVER4-LEFT") (pin "4") (pinfunction "1_4") (pintype "passive"))
      (node (ref "DRIVER5-LEFT") (pin "4") (pinfunction "1_4") (pintype "passive"))
      (node (ref "DRIVER6-LEFT") (pin "4") (pinfunction "1_4") (pintype "passive"))
      (node (ref "MS3") (pin "1") (pinfunction "1_1") (pintype "passive"))
    )
    (net (code "58") (name "Net-(DRIVER1-LEFTE-1)") (class "Default")
      (node (ref "!RST") (pin "1") (pinfunction "1_1") (pintype "passive"))
      (node (ref "DRIVER1-LEFT") (pin "5") (pinfunction "1_5") (pintype "passive"))
      (node (ref "DRIVER2-LEFT") (pin "5") (pinfunction "1_5") (pintype "passive"))
      (node (ref "DRIVER3-LEFT") (pin "5") (pinfunction "1_5") (pintype "passive"))
      (node (ref "DRIVER4-LEFT") (pin "5") (pinfunction "1_5") (pintype "passive"))
      (node (ref "DRIVER5-LEFT") (pin "5") (pinfunction "1_5") (pintype "passive"))
      (node (ref "DRIVER6-LEFT") (pin "5") (pinfunction "1_5") (pintype "passive"))
    )
    (net (code "59") (name "Net-(DRIVER1-LEFTG-1)") (class "Default")
      (node (ref "DRIVER1-LEFT") (pin "7") (pinfunction "1_7") (pintype "passive"))
      (node (ref "DRIVER2-LEFT") (pin "7") (pinfunction "1_7") (pintype "passive"))
      (node (ref "DRIVER3-LEFT") (pin "7") (pinfunction "1_7") (pintype "passive"))
      (node (ref "DRIVER4-LEFT") (pin "7") (pinfunction "1_7") (pintype "passive"))
      (node (ref "DRIVER5-LEFT") (pin "7") (pinfunction "1_7") (pintype "passive"))
      (node (ref "DRIVER6-LEFT") (pin "7") (pinfunction "1_7") (pintype "passive"))
      (node (ref "STEP") (pin "1") (pinfunction "1_1") (pintype "passive"))
    )
    (net (code "60") (name "Net-(DRIVER1-LEFTH-1)") (class "Default")
      (node (ref "DIR") (pin "1") (pinfunction "1_1") (pintype "passive"))
      (node (ref "DRIVER1-LEFT") (pin "8") (pinfunction "1_8") (pintype "passive"))
      (node (ref "DRIVER2-LEFT") (pin "8") (pinfunction "1_8") (pintype "passive"))
      (node (ref "DRIVER3-LEFT") (pin "8") (pinfunction "1_8") (pintype "passive"))
      (node (ref "DRIVER4-LEFT") (pin "8") (pinfunction "1_8") (pintype "passive"))
      (node (ref "DRIVER5-LEFT") (pin "8") (pinfunction "1_8") (pintype "passive"))
      (node (ref "DRIVER6-LEFT") (pin "8") (pinfunction "1_8") (pintype "passive"))
    )
    (net (code "61") (name "unconnected-(DEMUX_CHANNEL_AA-X3-Pad12)") (class "Default")
      (node (ref "DEMUX_CHANNEL_A") (pin "12") (pinfunction "X3_12") (pintype "bidirectional"))
    )
    (net (code "62") (name "unconnected-(DEMUX_CHANNEL_AA-X7-Pad4)") (class "Default")
      (node (ref "DEMUX_CHANNEL_A") (pin "4") (pinfunction "X7_4") (pintype "bidirectional"))
    )
    (net (code "63") (name "unconnected-(DEMUX_CHANNEL_BA-X3-Pad12)") (class "Default")
      (node (ref "DEMUX_CHANNEL_B") (pin "12") (pinfunction "X3_12") (pintype "bidirectional"))
    )
    (net (code "64") (name "unconnected-(DEMUX_CHANNEL_BA-X7-Pad4)") (class "Default")
      (node (ref "DEMUX_CHANNEL_B") (pin "4") (pinfunction "X7_4") (pintype "bidirectional"))
    )
    (net (code "65") (name "unconnected-(ENCODEUR1-Pad2)") (class "Default")
      (node (ref "ENCODEUR1") (pin "2") (pinfunction "2_2") (pintype "passive"))
    )
    (net (code "66") (name "unconnected-(ENCODEUR2-Pad2)") (class "Default")
      (node (ref "ENCODEUR2") (pin "2") (pinfunction "2_2") (pintype "passive"))
    )
    (net (code "67") (name "unconnected-(ENCODEUR3-Pad2)") (class "Default")
      (node (ref "ENCODEUR3") (pin "2") (pinfunction "2_2") (pintype "passive"))
    )
    (net (code "68") (name "unconnected-(ENCODEUR4-Pad2)") (class "Default")
      (node (ref "ENCODEUR4") (pin "2") (pinfunction "2_2") (pintype "passive"))
    )
    (net (code "69") (name "unconnected-(ENCODEUR5-Pad2)") (class "Default")
      (node (ref "ENCODEUR5") (pin "2") (pinfunction "2_2") (pintype "passive"))
    )
    (net (code "70") (name "unconnected-(ENCODEUR6-Pad2)") (class "Default")
      (node (ref "ENCODEUR6") (pin "2") (pinfunction "2_2") (pintype "passive"))
    )
  )
)
